# ProPrj_CGM_BH66F2452_HT32F67595_V1_0.net
KiCad netlist of a schematic drawn in EasyEDA Pro
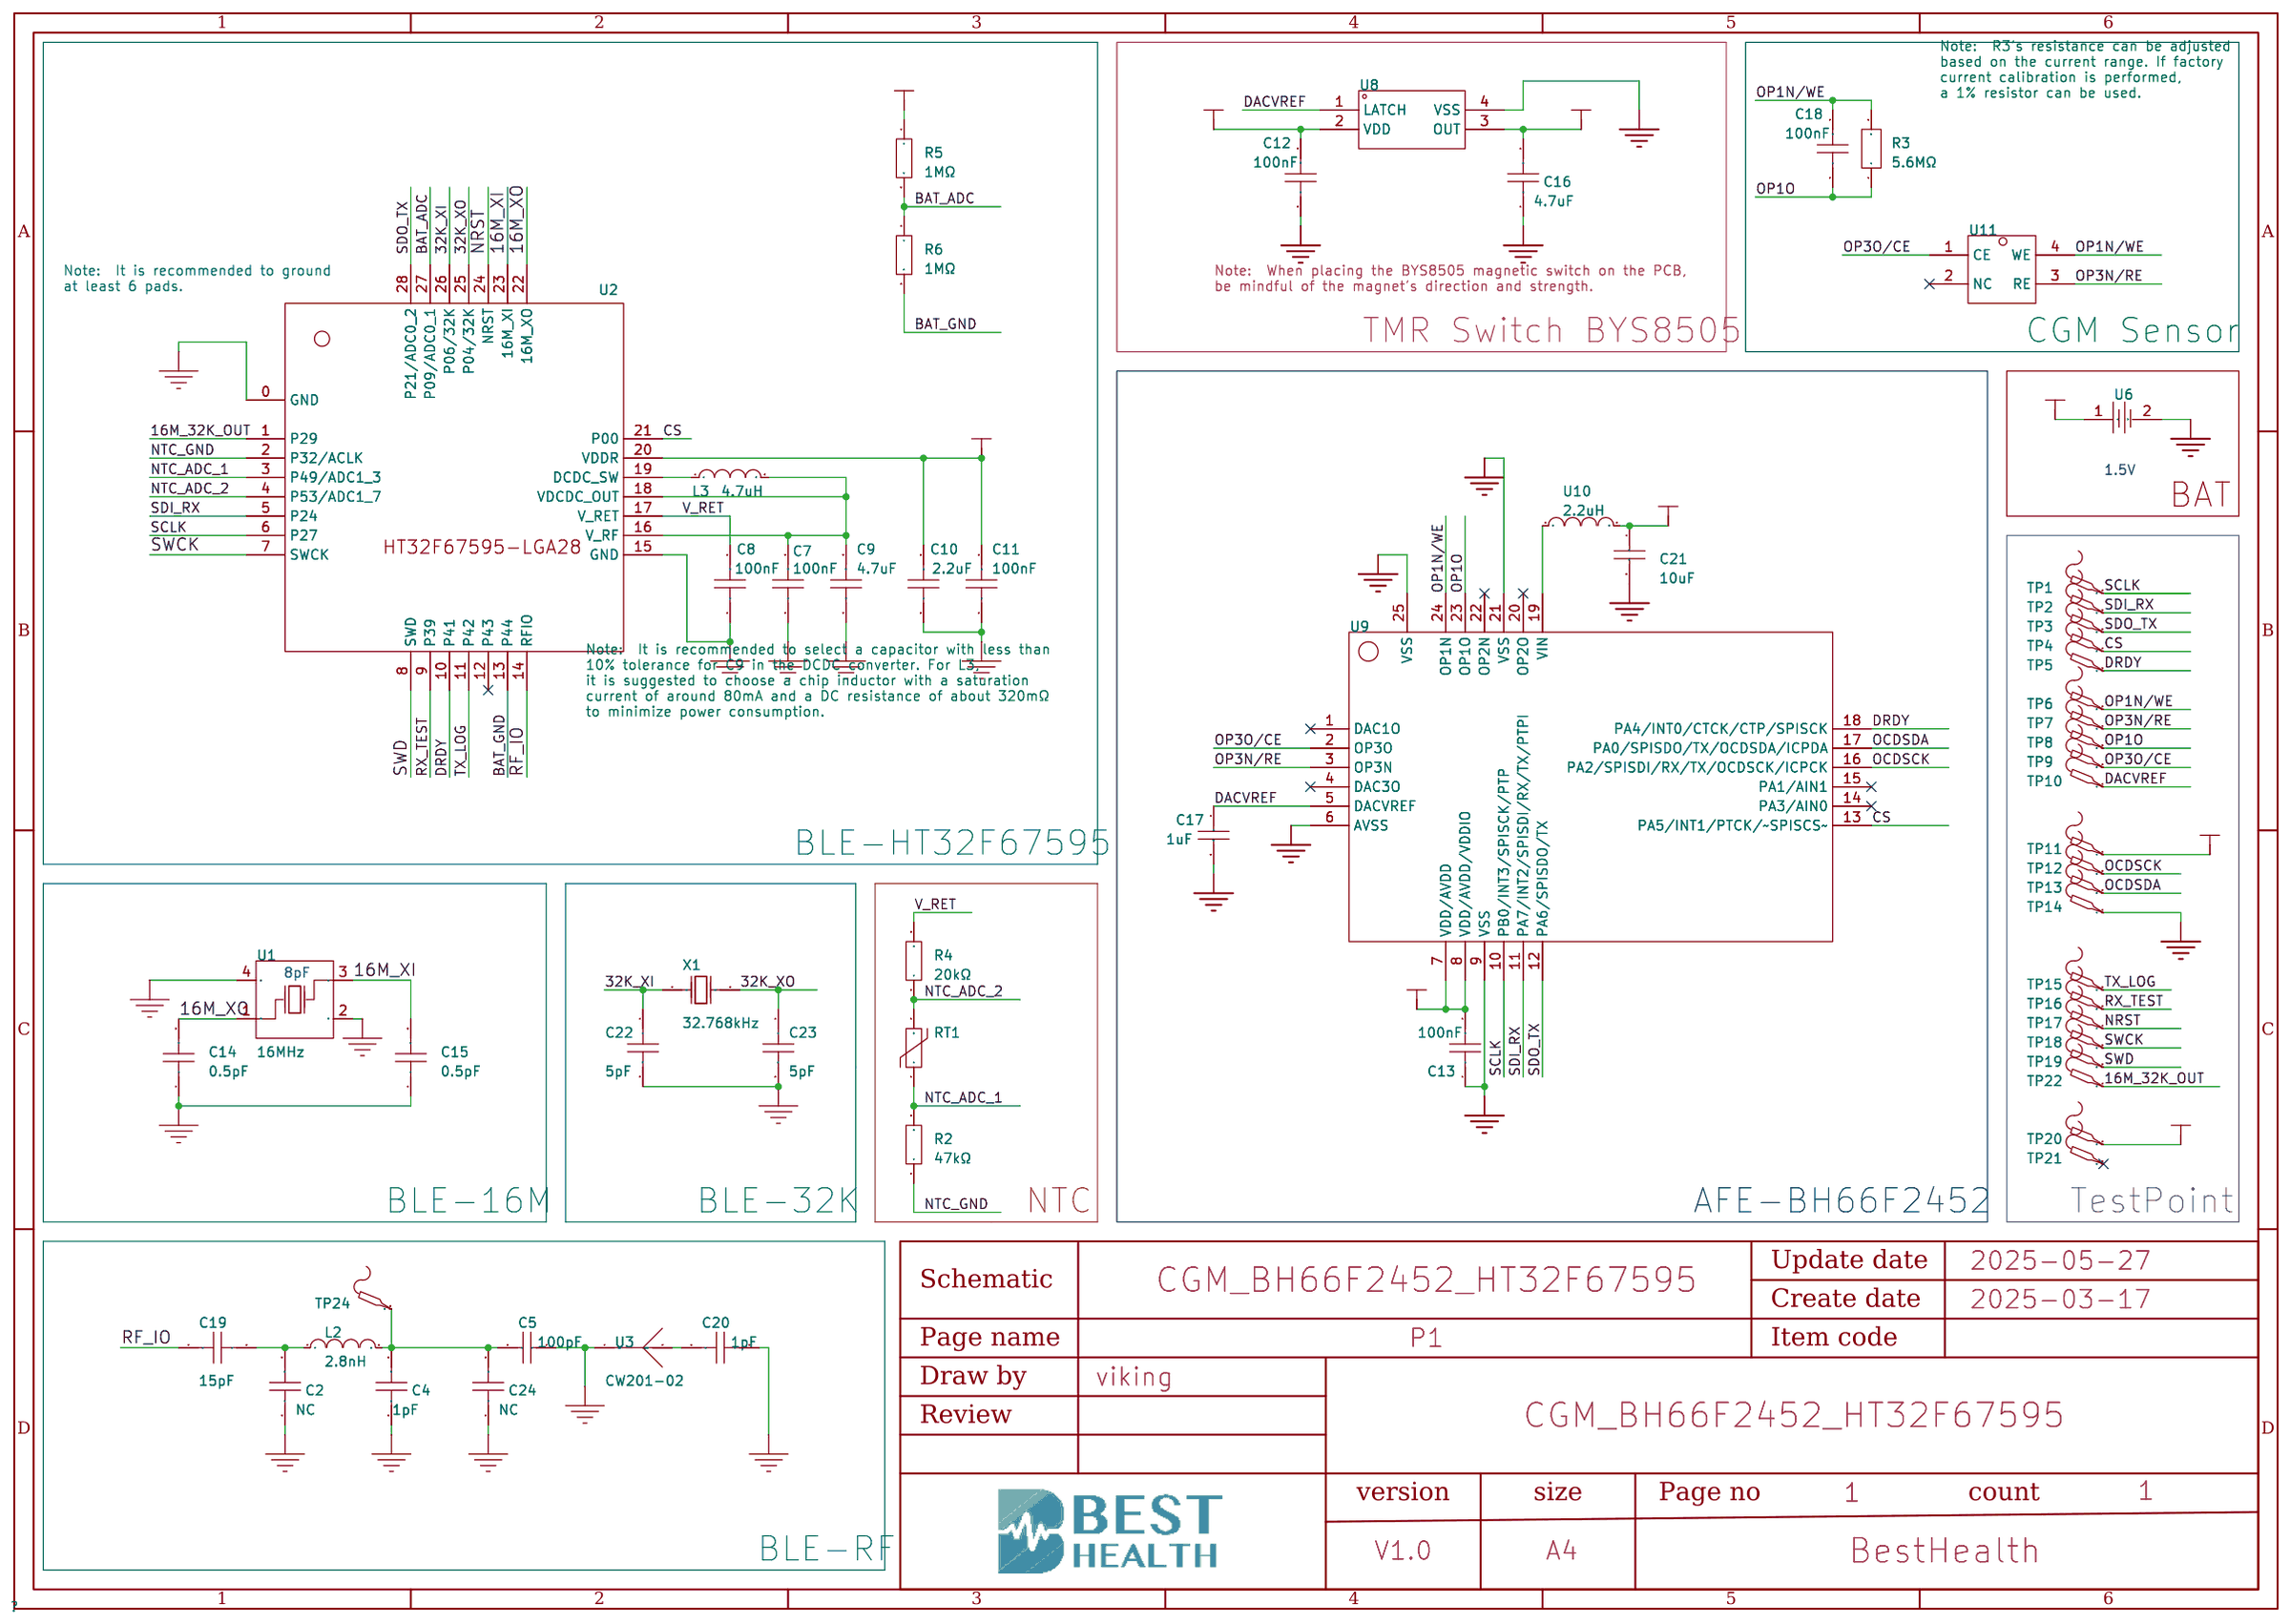
[diagram p0: schematic sheet]

(export (version "E")
  (design (tool "Eeschema 10.0.6"))
  (components
    (comp (ref "C2")
      (value "1.2pF")
      (footprint "easyedapro:C0201")
      (description "容值:1.2pF;额定电压:50V;材质(温度系数):C0G;")
      (fields
        (field (name "Manufacturer Part") "GJM0335C1H1R2WB01D")
        (field (name "Manufacturer") "muRata(村田)")
      )
      (libsource (lib "easyedapro") (part "GJM0335C1H1R2WB01D"))
    )
    (comp (ref "C4")
      (value "1pF")
      (footprint "easyedapro:C0201")
      (description "容值:1pF;精度:-;额定电压:50V;材质(温度系数):C0G;")
      (fields
        (field (name "Manufacturer Part") "GRM0335C1H1R0BA01D")
        (field (name "Manufacturer") "muRata(村田)")
      )
      (libsource (lib "easyedapro") (part "GRM0335C1H1R0BA01D"))
    )
    (comp (ref "C5")
      (value "100pF")
      (footprint "easyedapro:C0201")
      (description "容值:100pF;精度:±5%;额定电压:50V;材质(温度系数):C0G;")
      (fields
        (field (name "Manufacturer Part") "GRM0335C1H101JA01D")
        (field (name "Manufacturer") "muRata(村田)")
      )
      (libsource (lib "easyedapro") (part "GRM0335C1H101JA01D"))
    )
    (comp (ref "C7")
      (value "100nF")
      (footprint "easyedapro:C0201")
      (description "容值:100nF;精度:±10%;额定电压:16V;材质(温度系数):X5R;")
      (fields
        (field (name "Manufacturer Part") "CL03A104KO3NNNC")
        (field (name "Manufacturer") "SAMSUNG(三星)")
      )
      (libsource (lib "easyedapro") (part "CL03A104KO3NNNC"))
    )
    (comp (ref "C8")
      (value "100nF")
      (footprint "easyedapro:C0201")
      (description "容值:100nF;精度:±10%;额定电压:16V;材质(温度系数):X5R;")
      (fields
        (field (name "Manufacturer Part") "CL03A104KO3NNNC")
        (field (name "Manufacturer") "SAMSUNG(三星)")
      )
      (libsource (lib "easyedapro") (part "CL03A104KO3NNNC"))
    )
    (comp (ref "C9")
      (value "4.7uF")
      (footprint "easyedapro:C0402")
      (description "容值:4.7uF;精度:±10%;额定电压:10V;材质(温度系数):X5R;")
      (fields
        (field (name "Manufacturer Part") "CL05A475KP5NRNC")
        (field (name "Manufacturer") "SAMSUNG(三星)")
      )
      (libsource (lib "easyedapro") (part "CL05A475KP5NRNC"))
    )
    (comp (ref "C10")
      (value "2.2uF")
      (footprint "easyedapro:C0201")
      (description "容值:2.2uF;精度:±20%;额定电压:10V;材质(温度系数):X5R;")
      (fields
        (field (name "Manufacturer Part") "GRM033R61A225ME47D")
        (field (name "Manufacturer") "muRata(村田)")
      )
      (libsource (lib "easyedapro") (part "GRM033R61A225ME47D"))
    )
    (comp (ref "C11")
      (value "100nF")
      (footprint "easyedapro:C0201")
      (description "容值:100nF;精度:±10%;额定电压:16V;材质(温度系数):X5R;")
      (fields
        (field (name "Manufacturer Part") "CL03A104KO3NNNC")
        (field (name "Manufacturer") "SAMSUNG(三星)")
      )
      (libsource (lib "easyedapro") (part "CL03A104KO3NNNC"))
    )
    (comp (ref "C12")
      (value "100nF")
      (footprint "easyedapro:C0201")
      (description "容值:100nF;精度:±10%;额定电压:16V;材质(温度系数):X5R;")
      (fields
        (field (name "Manufacturer Part") "CL03A104KO3NNNC")
        (field (name "Manufacturer") "SAMSUNG(三星)")
      )
      (libsource (lib "easyedapro") (part "CL03A104KO3NNNC"))
    )
    (comp (ref "C13")
      (value "100nF")
      (footprint "easyedapro:C0201")
      (description "容值:100nF;精度:±10%;额定电压:16V;材质(温度系数):X5R;")
      (fields
        (field (name "Manufacturer Part") "CL03A104KO3NNNC")
        (field (name "Manufacturer") "SAMSUNG(三星)")
      )
      (libsource (lib "easyedapro") (part "CL03A104KO3NNNC"))
    )
    (comp (ref "C14")
      (value "0.5pF")
      (footprint "easyedapro:C0201")
      (description "容值:0.5pF;额定电压:50V;温度系数:C0G;")
      (fields
        (field (name "Manufacturer Part") "GRM0335C1HR50BA01D")
        (field (name "Manufacturer") "muRata(村田)")
      )
      (libsource (lib "easyedapro") (part "GRM0335C1HR50BA01D"))
    )
    (comp (ref "C15")
      (value "0.5pF")
      (footprint "easyedapro:C0201")
      (description "容值:0.5pF;额定电压:50V;温度系数:C0G;")
      (fields
        (field (name "Manufacturer Part") "GRM0335C1HR50BA01D")
        (field (name "Manufacturer") "muRata(村田)")
      )
      (libsource (lib "easyedapro") (part "GRM0335C1HR50BA01D"))
    )
    (comp (ref "C16")
      (value "4.7uF")
      (footprint "easyedapro:C0201")
      (description "容值:4.7uF;精度:±20%;额定电压:6.3V;材质(温度系数):X5R;")
      (fields
        (field (name "Manufacturer Part") "GRM035R60J475ME15D")
        (field (name "Manufacturer") "muRata(村田)")
      )
      (libsource (lib "easyedapro") (part "GRM035R60J475ME15D"))
    )
    (comp (ref "C17")
      (value "1uF")
      (footprint "easyedapro:C0201")
      (description "容值:1uF;精度:±20%;额定电压:6.3V;材质(温度系数):X5R;")
      (fields
        (field (name "Manufacturer Part") "CL03A105MQ3CSNH")
        (field (name "Manufacturer") "SAMSUNG(三星)")
      )
      (libsource (lib "easyedapro") (part "CL03A105MQ3CSNH"))
    )
    (comp (ref "C18")
      (value "100nF")
      (footprint "easyedapro:C0201")
      (description "容值:100nF;精度:±10%;额定电压:16V;材质(温度系数):X5R;")
      (fields
        (field (name "Manufacturer Part") "CL03A104KO3NNNC")
        (field (name "Manufacturer") "SAMSUNG(三星)")
      )
      (libsource (lib "easyedapro") (part "CL03A104KO3NNNC"))
    )
    (comp (ref "C19")
      (value "15pF")
      (footprint "easyedapro:C0201")
      (description "容值:15pF;精度:±5%;额定电压:50V;温度系数:C0G;")
      (fields
        (field (name "Manufacturer Part") "GRM0335C1H150JA01D")
        (field (name "Manufacturer") "muRata(村田)")
      )
      (libsource (lib "easyedapro") (part "GRM0335C1H150JA01D"))
    )
    (comp (ref "C20")
      (value "1pF")
      (footprint "easyedapro:C0201")
      (description "容值:1pF;精度:-;额定电压:50V;材质(温度系数):C0G;")
      (fields
        (field (name "Manufacturer Part") "GRM0335C1H1R0BA01D")
        (field (name "Manufacturer") "muRata(村田)")
      )
      (libsource (lib "easyedapro") (part "GRM0335C1H1R0BA01D"))
    )
    (comp (ref "C21")
      (value "10uF")
      (footprint "easyedapro:C0402")
      (description "容值:10uF;精度:±20%;额定电压:6.3V;材质(温度系数):X5R;")
      (fields
        (field (name "Manufacturer Part") "CL05A106MQ5NUNC")
        (field (name "Manufacturer") "SAMSUNG(三星)")
      )
      (libsource (lib "easyedapro") (part "CL05A106MQ5NUNC"))
    )
    (comp (ref "C22")
      (value "5pF")
      (footprint "easyedapro:C0201")
      (description "容值:5pF;额定电压:25V;材质(温度系数):C0G;")
      (fields
        (field (name "Manufacturer Part") "GJM0335C1E5R0BB01D")
        (field (name "Manufacturer") "muRata(村田)")
      )
      (libsource (lib "easyedapro") (part "GJM0335C1E5R0BB01D"))
    )
    (comp (ref "C23")
      (value "5pF")
      (footprint "easyedapro:C0201")
      (description "容值:5pF;额定电压:25V;材质(温度系数):C0G;")
      (fields
        (field (name "Manufacturer Part") "GJM0335C1E5R0BB01D")
        (field (name "Manufacturer") "muRata(村田)")
      )
      (libsource (lib "easyedapro") (part "GJM0335C1E5R0BB01D"))
    )
    (comp (ref "C24")
      (value "1.2pF")
      (footprint "easyedapro:C0201")
      (description "容值:1.2pF;额定电压:50V;材质(温度系数):C0G;")
      (fields
        (field (name "Manufacturer Part") "GJM0335C1H1R2WB01D")
        (field (name "Manufacturer") "muRata(村田)")
      )
      (libsource (lib "easyedapro") (part "GJM0335C1H1R2WB01D"))
    )
    (comp (ref "L2")
      (value "2.8nH")
      (footprint "easyedapro:L0201-RD")
      (description "电感值:2.8nH;精度:-;额定电流:450mA;饱和电流(Isat):-;直流电阻(DCR):250mΩ;")
      (fields (field (name "Manufacturer Part") "LQP03TG2N8B02D") (field (name "Manufacturer") "muRata(村田)"))
      (libsource (lib "easyedapro") (part "LQP03TG2N8B02D"))
    )
    (comp (ref "L3")
      (value "4.7uH")
      (footprint "easyedapro:L0603")
      (description "电感值:4.7uH;精度:±20%;额定电流:-;饱和电流(Isat):80mA;直流电阻(DCR):320mΩ;")
      (fields (field (name "Manufacturer Part") "MLZ1608N4R7LT000") (field (name "Manufacturer") "TDK"))
      (libsource (lib "easyedapro") (part "MLZ1608N4R7LT000"))
    )
    (comp (ref "R2")
      (value "47kΩ")
      (footprint "easyedapro:R0201")
      (description "电阻类型:厚膜电阻;阻值:47kΩ;精度:±1%;功率:50mW;温度系数:±200ppm/°C;最大工作电压:25V;工作温度范围:-55°C~+155°C;")
      (fields (field (name "Manufacturer Part") "RC0201FR-0747KL") (field (name "Manufacturer") "YAGEO(国巨)"))
      (libsource (lib "easyedapro") (part "RC0201FR-0747KL"))
    )
    (comp (ref "R3")
      (value "5.6MΩ")
      (footprint "easyedapro:R0402")
      (description "电阻类型:厚膜电阻;阻值:5.6MΩ;精度:±1%;功率:62.5mW;最大工作电压:50V;温度系数:±100ppm/°C;")
      (fields (field (name "Manufacturer Part") "RC0402FR-075M6L") (field (name "Manufacturer") "YAGEO(国巨)"))
      (libsource (lib "easyedapro") (part "RC0402FR-075M6L"))
    )
    (comp (ref "R4")
      (value "20kΩ")
      (footprint "easyedapro:R0201")
      (description "电阻类型:厚膜电阻;阻值:20kΩ;精度:±1%;功率:50mW;最大工作电压:25V;温度系数:±200ppm/°C;")
      (fields (field (name "Manufacturer Part") "RC0201FR-0720KL") (field (name "Manufacturer") "YAGEO(国巨)"))
      (libsource (lib "easyedapro") (part "RC0201FR-0720KL_C295787"))
    )
    (comp (ref "R5")
      (value "1MΩ")
      (footprint "easyedapro:R0201")
      (description "电阻类型:厚膜电阻;阻值:1MΩ;精度:±1%;功率:50mW;最大工作电压:25V;温度系数:±200ppm/°C;")
      (fields (field (name "Manufacturer Part") "RC0201FR-071ML") (field (name "Manufacturer") "YAGEO(国巨)"))
      (libsource (lib "easyedapro") (part "RC0201FR-071ML"))
    )
    (comp (ref "R6")
      (value "1MΩ")
      (footprint "easyedapro:R0201")
      (description "电阻类型:厚膜电阻;阻值:1MΩ;精度:±1%;功率:50mW;最大工作电压:25V;温度系数:±200ppm/°C;")
      (fields (field (name "Manufacturer Part") "RC0201FR-071ML") (field (name "Manufacturer") "YAGEO(国巨)"))
      (libsource (lib "easyedapro") (part "RC0201FR-071ML"))
    )
    (comp (ref "RT1")
      (value "NTCG064BF473FTBX")
      (footprint "easyedapro:R0201")
      (description "阻值(25°C):47kΩ;电阻精度:±1%;B值精度:±1%;B值(25°C/50°C):4050K;功率:100mW;最大稳态电流(25°C):140uA;")
      (fields (field (name "Manufacturer") "TDK"))
      (libsource (lib "easyedapro") (part "NTCG064BF473FTBX"))
    )
    (comp (ref "TP1")
      (value "TP1")
      (footprint "easyedapro:Test-Point-0.5mm")
      (description "Test Point 测试点")
      (libsource (lib "easyedapro") (part "Test-Point"))
    )
    (comp (ref "TP2")
      (value "TP1")
      (footprint "easyedapro:Test-Point-0.5mm")
      (description "Test Point 测试点")
      (libsource (lib "easyedapro") (part "Test-Point"))
    )
    (comp (ref "TP3")
      (value "TP1")
      (footprint "easyedapro:Test-Point-0.5mm")
      (description "Test Point 测试点")
      (libsource (lib "easyedapro") (part "Test-Point"))
    )
    (comp (ref "TP4")
      (value "TP1")
      (footprint "easyedapro:Test-Point-0.5mm")
      (description "Test Point 测试点")
      (libsource (lib "easyedapro") (part "Test-Point"))
    )
    (comp (ref "TP5")
      (value "TP1")
      (footprint "easyedapro:Test-Point-0.5mm")
      (description "Test Point 测试点")
      (libsource (lib "easyedapro") (part "Test-Point"))
    )
    (comp (ref "TP6")
      (value "TP1")
      (footprint "easyedapro:Test-Point-0.5mm")
      (description "Test Point 测试点")
      (libsource (lib "easyedapro") (part "Test-Point"))
    )
    (comp (ref "TP7")
      (value "TP1")
      (footprint "easyedapro:Test-Point-0.5mm")
      (description "Test Point 测试点")
      (libsource (lib "easyedapro") (part "Test-Point"))
    )
    (comp (ref "TP8")
      (value "TP1")
      (footprint "easyedapro:Test-Point-0.5mm")
      (description "Test Point 测试点")
      (libsource (lib "easyedapro") (part "Test-Point"))
    )
    (comp (ref "TP9")
      (value "TP1")
      (footprint "easyedapro:Test-Point-0.5mm")
      (description "Test Point 测试点")
      (libsource (lib "easyedapro") (part "Test-Point"))
    )
    (comp (ref "TP10")
      (value "TP1")
      (footprint "easyedapro:Test-Point-0.5mm")
      (description "Test Point 测试点")
      (libsource (lib "easyedapro") (part "Test-Point"))
    )
    (comp (ref "TP11")
      (value "TP1")
      (footprint "easyedapro:Test-Point-0.5mm")
      (description "Test Point 测试点")
      (libsource (lib "easyedapro") (part "Test-Point"))
    )
    (comp (ref "TP12")
      (value "TP1")
      (footprint "easyedapro:Test-Point-0.5mm")
      (description "Test Point 测试点")
      (libsource (lib "easyedapro") (part "Test-Point"))
    )
    (comp (ref "TP13")
      (value "TP1")
      (footprint "easyedapro:Test-Point-0.5mm")
      (description "Test Point 测试点")
      (libsource (lib "easyedapro") (part "Test-Point"))
    )
    (comp (ref "TP14")
      (value "TP1")
      (footprint "easyedapro:Test-Point-0.5mm")
      (description "Test Point 测试点")
      (libsource (lib "easyedapro") (part "Test-Point"))
    )
    (comp (ref "TP15")
      (value "~")
      (footprint "easyedapro:Test-Point-0.5mm")
      (description "Test Point 测试点")
      (libsource (lib "easyedapro") (part "Test-Point"))
    )
    (comp (ref "TP16")
      (value "~")
      (footprint "easyedapro:Test-Point-0.5mm")
      (description "Test Point 测试点")
      (libsource (lib "easyedapro") (part "Test-Point"))
    )
    (comp (ref "TP17")
      (value "~")
      (footprint "easyedapro:Test-Point-0.5mm")
      (description "Test Point 测试点")
      (libsource (lib "easyedapro") (part "Test-Point"))
    )
    (comp (ref "TP18")
      (value "~")
      (footprint "easyedapro:Test-Point-0.5mm")
      (description "Test Point 测试点")
      (libsource (lib "easyedapro") (part "Test-Point"))
    )
    (comp (ref "TP19")
      (value "~")
      (footprint "easyedapro:Test-Point-0.5mm")
      (description "Test Point 测试点")
      (libsource (lib "easyedapro") (part "Test-Point"))
    )
    (comp (ref "TP20")
      (value "~")
      (footprint "easyedapro:Test-Point-0.5mm")
      (description "Test Point 测试点")
      (libsource (lib "easyedapro") (part "Test-Point"))
    )
    (comp (ref "TP21")
      (value "~")
      (footprint "easyedapro:Test-Point-0.5mm")
      (description "Test Point 测试点")
      (libsource (lib "easyedapro") (part "Test-Point"))
    )
    (comp (ref "TP22")
      (value "~")
      (footprint "easyedapro:Test-Point-0.5mm")
      (description "Test Point 测试点")
      (libsource (lib "easyedapro") (part "Test-Point"))
    )
    (comp (ref "TP24")
      (value "~")
      (footprint "easyedapro:Test-Point-0.5mm")
      (description "Test Point 测试点")
      (libsource (lib "easyedapro") (part "Test-Point"))
    )
    (comp (ref "U1")
      (value "16MHz")
      (footprint "easyedapro:CRYSTAL-SMD_4P-L2.0-W1.6-BL-A")
      (description "频率:16MHz;负载电容:8pF;频率公差:±10ppm;")
      (fields
        (field (name "Manufacturer Part") "XL7EL89CKI-111YLC-16M")
        (field (name "Manufacturer") "YXC(扬兴晶振)")
      )
      (libsource (lib "easyedapro") (part "XL7EL89CKI-111YLC-16M"))
    )
    (comp (ref "U2")
      (value "HT32F67595_LGA28")
      (footprint "easyedapro:LGA28_L3.0_W3.0mm")
      (libsource (lib "easyedapro") (part "HT32F67595_LGA28"))
    )
    (comp (ref "U3")
      (value "CW201-02")
      (footprint "easyedapro:ANT-SMD_L2.0-W1.2_CW201")
      (fields (field (name "Manufacturer") "LXC(连兴创)"))
      (libsource (lib "easyedapro") (part "CW201-02"))
    )
    (comp (ref "U6")
      (value "~")
      (footprint "easyedapro:SR716")
      (description "氧化銀紐扣電池1.5V")
      (libsource (lib "easyedapro") (part "SR716"))
    )
    (comp (ref "U8")
      (value "~")
      (footprint "easyedapro:LGA-4_L1.5-W1.5-P0.65-BL")
      (libsource (lib "easyedapro") (part "BYS8505"))
    )
    (comp (ref "U9")
      (value "~")
      (footprint "easyedapro:WQFN-24_L3.0-W3.0-P0.40-TL-EP1.9")
      (description "该单片机是一款 A/D 型具有 8 位高性能精简指令集的 Flash 单片机，内置连续\n血糖监测 AFE 模块，专门为连续血糖监测产品而设计。")
      (fields (field (name "Manufacturer") "HOLTEK"))
      (libsource (lib "easyedapro") (part "BH66F2452"))
    )
    (comp (ref "U10")
      (value "2.2uH")
      (footprint "easyedapro:IND-SMD_L2.0-W1.6")
      (description "电感值:2.2uH;精度:±20%;额定电流:1.31A;饱和电流(Isat):1.31A;")
      (fields (field (name "Manufacturer Part") "VLS201610CX-2R2M-1") (field (name "Manufacturer") "TDK"))
      (libsource (lib "easyedapro") (part "VLS201610CX-2R2M-1"))
    )
    (comp (ref "U11")
      (value "~")
      (footprint "easyedapro:CGM_Sener_V2_TBJ")
      (libsource (lib "easyedapro") (part "CGM_Sensor_V2_TBJ"))
    )
    (comp (ref "X1")
      (value "32.768kHz")
      (footprint "easyedapro:CRYSTAL-SMD_L1.7-W1.1")
      (description "频率:32.768kHz;外接负载电容:12.5pF;")
      (fields (field (name "Manufacturer Part") "X1A0001210005") (field (name "Manufacturer") "EPSON(爱普生)"))
      (libsource (lib "easyedapro") (part "X1A000121000500"))
    )
  )
  (nets
    (net (code "1") (name "/16M_32K_OUT") (class "Default")
      (node (ref "TP22") (pin "1") (pinfunction "1_1") (pintype "input"))
      (node (ref "U2") (pin "1") (pinfunction "P29_1") (pintype "input"))
    )
    (net (code "2") (name "/16M_XI") (class "Default")
      (node (ref "C15") (pin "2") (pinfunction "2_2") (pintype "unspecified"))
      (node (ref "U1") (pin "3") (pinfunction "OSC2_3") (pintype "unspecified"))
      (node (ref "U2") (pin "23") (pinfunction "16M_XI_23") (pintype "input"))
    )
    (net (code "3") (name "/16M_XO") (class "Default")
      (node (ref "C14") (pin "2") (pinfunction "2_2") (pintype "unspecified"))
      (node (ref "U1") (pin "1") (pinfunction "OSC1_1") (pintype "unspecified"))
      (node (ref "U2") (pin "22") (pinfunction "16M_XO_22") (pintype "input"))
    )
    (net (code "4") (name "/32K_XI") (class "Default")
      (node (ref "C22") (pin "1") (pinfunction "1_1") (pintype "unspecified"))
      (node (ref "U2") (pin "26") (pinfunction "P06/32K_26") (pintype "input"))
      (node (ref "X1") (pin "1") (pinfunction "OSC1_1") (pintype "input"))
    )
    (net (code "5") (name "/32K_XO") (class "Default")
      (node (ref "C23") (pin "1") (pinfunction "1_1") (pintype "unspecified"))
      (node (ref "U2") (pin "25") (pinfunction "P04/32K_25") (pintype "input"))
      (node (ref "X1") (pin "2") (pinfunction "OSC2_2") (pintype "input"))
    )
    (net (code "6") (name "/BAT_ADC") (class "Default")
      (node (ref "R5") (pin "2") (pinfunction "2_2") (pintype "unspecified"))
      (node (ref "R6") (pin "1") (pinfunction "1_1") (pintype "unspecified"))
      (node (ref "U2") (pin "27") (pinfunction "P09/ADC0_1_27") (pintype "input"))
    )
    (net (code "7") (name "/BAT_GND") (class "Default")
      (node (ref "R6") (pin "2") (pinfunction "2_2") (pintype "unspecified"))
      (node (ref "U2") (pin "13") (pinfunction "P44_13") (pintype "input"))
    )
    (net (code "8") (name "/CS") (class "Default")
      (node (ref "TP4") (pin "1") (pinfunction "1_1") (pintype "input"))
      (node (ref "U2") (pin "21") (pinfunction "P00_21") (pintype "input"))
      (node (ref "U9") (pin "13") (pinfunction "PA5/INT1/PTCK/~SPISCS~_13") (pintype "input"))
    )
    (net (code "9") (name "/DACVREF") (class "Default")
      (node (ref "C17") (pin "1") (pinfunction "1_1") (pintype "input"))
      (node (ref "TP10") (pin "1") (pinfunction "1_1") (pintype "input"))
      (node (ref "U8") (pin "1") (pinfunction "LATCH_1") (pintype "input"))
      (node (ref "U9") (pin "5") (pinfunction "DACVREF_5") (pintype "input"))
    )
    (net (code "10") (name "/DRDY") (class "Default")
      (node (ref "TP5") (pin "1") (pinfunction "1_1") (pintype "input"))
      (node (ref "U2") (pin "10") (pinfunction "P41_10") (pintype "input"))
      (node (ref "U9") (pin "18") (pinfunction "PA4/INT0/CTCK/CTP/SPISCK_18") (pintype "input"))
    )
    (net (code "11") (name "/NRST") (class "Default")
      (node (ref "TP17") (pin "1") (pinfunction "1_1") (pintype "input"))
      (node (ref "U2") (pin "24") (pinfunction "NRST_24") (pintype "input"))
    )
    (net (code "12") (name "/NTC_ADC_1") (class "Default")
      (node (ref "R2") (pin "2") (pinfunction "2_2") (pintype "input"))
      (node (ref "RT1") (pin "1") (pinfunction "1_1") (pintype "input"))
      (node (ref "U2") (pin "3") (pinfunction "P49/ADC1_3_3") (pintype "input"))
    )
    (net (code "13") (name "/NTC_ADC_2") (class "Default")
      (node (ref "R4") (pin "1") (pinfunction "1_1") (pintype "unspecified"))
      (node (ref "RT1") (pin "2") (pinfunction "2_2") (pintype "input"))
      (node (ref "U2") (pin "4") (pinfunction "P53/ADC1_7_4") (pintype "input"))
    )
    (net (code "14") (name "/NTC_GND") (class "Default")
      (node (ref "R2") (pin "1") (pinfunction "1_1") (pintype "input"))
      (node (ref "U2") (pin "2") (pinfunction "P32/ACLK_2") (pintype "input"))
    )
    (net (code "15") (name "/OCDSCK") (class "Default")
      (node (ref "TP12") (pin "1") (pinfunction "1_1") (pintype "input"))
      (node (ref "U9") (pin "16") (pinfunction "PA2/SPISDI/RX/TX/OCDSCK/ICPCK_16") (pintype "input"))
    )
    (net (code "16") (name "/OCDSDA") (class "Default")
      (node (ref "TP13") (pin "1") (pinfunction "1_1") (pintype "input"))
      (node (ref "U9") (pin "17") (pinfunction "PA0/SPISDO/TX/OCDSDA/ICPDA_17") (pintype "input"))
    )
    (net (code "17") (name "/OP1N{slash}WE") (class "Default")
      (node (ref "C18") (pin "2") (pinfunction "2_2") (pintype "input"))
      (node (ref "R3") (pin "2") (pinfunction "2_2") (pintype "unspecified"))
      (node (ref "TP6") (pin "1") (pinfunction "1_1") (pintype "input"))
      (node (ref "U11") (pin "4") (pinfunction "WE_4") (pintype "input"))
      (node (ref "U9") (pin "24") (pinfunction "OP1N_24") (pintype "input"))
    )
    (net (code "18") (name "/OP1O") (class "Default")
      (node (ref "C18") (pin "1") (pinfunction "1_1") (pintype "input"))
      (node (ref "R3") (pin "1") (pinfunction "1_1") (pintype "unspecified"))
      (node (ref "TP8") (pin "1") (pinfunction "1_1") (pintype "input"))
      (node (ref "U9") (pin "23") (pinfunction "OP1O_23") (pintype "input"))
    )
    (net (code "19") (name "/OP3N{slash}RE") (class "Default")
      (node (ref "TP7") (pin "1") (pinfunction "1_1") (pintype "input"))
      (node (ref "U11") (pin "3") (pinfunction "RE_3") (pintype "input"))
      (node (ref "U9") (pin "3") (pinfunction "OP3N_3") (pintype "input"))
    )
    (net (code "20") (name "/OP3O{slash}CE") (class "Default")
      (node (ref "TP9") (pin "1") (pinfunction "1_1") (pintype "input"))
      (node (ref "U11") (pin "1") (pinfunction "CE_1") (pintype "input"))
      (node (ref "U9") (pin "2") (pinfunction "OP3O_2") (pintype "input"))
    )
    (net (code "21") (name "/RF_IO") (class "Default")
      (node (ref "C19") (pin "1") (pinfunction "1_1") (pintype "unspecified"))
      (node (ref "U2") (pin "14") (pinfunction "RFIO_14") (pintype "input"))
    )
    (net (code "22") (name "/RX_TEST") (class "Default")
      (node (ref "TP16") (pin "1") (pinfunction "1_1") (pintype "input"))
      (node (ref "U2") (pin "9") (pinfunction "P39_9") (pintype "input"))
    )
    (net (code "23") (name "/SCLK") (class "Default")
      (node (ref "TP1") (pin "1") (pinfunction "1_1") (pintype "input"))
      (node (ref "U2") (pin "6") (pinfunction "P27_6") (pintype "input"))
      (node (ref "U9") (pin "10") (pinfunction "PB0/INT3/SPISCK/PTP_10") (pintype "input"))
    )
    (net (code "24") (name "/SDI_RX") (class "Default")
      (node (ref "TP2") (pin "1") (pinfunction "1_1") (pintype "input"))
      (node (ref "U2") (pin "5") (pinfunction "P24_5") (pintype "input"))
      (node (ref "U9") (pin "11") (pinfunction "PA7/INT2/SPISDI/RX/TX/PTPI_11") (pintype "input"))
    )
    (net (code "25") (name "/SDO_TX") (class "Default")
      (node (ref "TP3") (pin "1") (pinfunction "1_1") (pintype "input"))
      (node (ref "U2") (pin "28") (pinfunction "P21/ADC0_2_28") (pintype "input"))
      (node (ref "U9") (pin "12") (pinfunction "PA6/SPISDO/TX_12") (pintype "input"))
    )
    (net (code "26") (name "/SWCK") (class "Default")
      (node (ref "TP18") (pin "1") (pinfunction "1_1") (pintype "input"))
      (node (ref "U2") (pin "7") (pinfunction "SWCK_7") (pintype "input"))
    )
    (net (code "27") (name "/SWD") (class "Default")
      (node (ref "TP19") (pin "1") (pinfunction "1_1") (pintype "input"))
      (node (ref "U2") (pin "8") (pinfunction "SWD_8") (pintype "input"))
    )
    (net (code "28") (name "/TX_LOG") (class "Default")
      (node (ref "TP15") (pin "1") (pinfunction "1_1") (pintype "input"))
      (node (ref "U2") (pin "11") (pinfunction "P42_11") (pintype "input"))
    )
    (net (code "29") (name "/V_RET") (class "Default")
      (node (ref "C8") (pin "2") (pinfunction "2_2") (pintype "input"))
      (node (ref "R4") (pin "2") (pinfunction "2_2") (pintype "unspecified"))
      (node (ref "U2") (pin "17") (pinfunction "V_RET_17") (pintype "input"))
    )
    (net (code "30") (name "GND") (class "Default")
      (node (ref "C10") (pin "1") (pinfunction "1_1") (pintype "unspecified"))
      (node (ref "C11") (pin "1") (pinfunction "1_1") (pintype "input"))
      (node (ref "C12") (pin "1") (pinfunction "1_1") (pintype "input"))
      (node (ref "C13") (pin "1") (pinfunction "1_1") (pintype "input"))
      (node (ref "C14") (pin "1") (pinfunction "1_1") (pintype "unspecified"))
      (node (ref "C15") (pin "1") (pinfunction "1_1") (pintype "unspecified"))
      (node (ref "C16") (pin "1") (pinfunction "1_1") (pintype "unspecified"))
      (node (ref "C17") (pin "2") (pinfunction "2_2") (pintype "input"))
      (node (ref "C2") (pin "1") (pinfunction "1_1") (pintype "unspecified"))
      (node (ref "C20") (pin "1") (pinfunction "1_1") (pintype "unspecified"))
      (node (ref "C21") (pin "2") (pinfunction "2_2") (pintype "input"))
      (node (ref "C22") (pin "2") (pinfunction "2_2") (pintype "unspecified"))
      (node (ref "C23") (pin "2") (pinfunction "2_2") (pintype "unspecified"))
      (node (ref "C24") (pin "1") (pinfunction "1_1") (pintype "unspecified"))
      (node (ref "C4") (pin "1") (pinfunction "1_1") (pintype "unspecified"))
      (node (ref "C5") (pin "2") (pinfunction "2_2") (pintype "input"))
      (node (ref "C7") (pin "1") (pinfunction "1_1") (pintype "input"))
      (node (ref "C8") (pin "1") (pinfunction "1_1") (pintype "input"))
      (node (ref "C9") (pin "1") (pinfunction "1_1") (pintype "unspecified"))
      (node (ref "TP14") (pin "1") (pinfunction "1_1") (pintype "input"))
      (node (ref "U1") (pin "2") (pinfunction "GND_2") (pintype "unspecified"))
      (node (ref "U1") (pin "4") (pinfunction "GND_4") (pintype "unspecified"))
      (node (ref "U2") (pin "0") (pinfunction "GND_0") (pintype "input"))
      (node (ref "U2") (pin "15") (pinfunction "GND_15") (pintype "input"))
      (node (ref "U3") (pin "1") (pinfunction "Signal_Input_1") (pintype "unspecified"))
      (node (ref "U6") (pin "2") (pinfunction "2_2") (pintype "input"))
      (node (ref "U8") (pin "4") (pinfunction "VSS_4") (pintype "input"))
      (node (ref "U9") (pin "21") (pinfunction "VSS_21") (pintype "input"))
      (node (ref "U9") (pin "25") (pinfunction "VSS_25") (pintype "input"))
      (node (ref "U9") (pin "6") (pinfunction "AVSS_6") (pintype "input"))
      (node (ref "U9") (pin "9") (pinfunction "VSS_9") (pintype "input"))
    )
    (net (code "31") (name "Net-(C19-Pad2)") (class "Default")
      (node (ref "C19") (pin "2") (pinfunction "2_2") (pintype "unspecified"))
      (node (ref "C2") (pin "2") (pinfunction "2_2") (pintype "unspecified"))
      (node (ref "L2") (pin "1") (pinfunction "1_1") (pintype "unspecified"))
    )
    (net (code "32") (name "Net-(C24-Pad2)") (class "Default")
      (node (ref "C24") (pin "2") (pinfunction "2_2") (pintype "unspecified"))
      (node (ref "C4") (pin "2") (pinfunction "2_2") (pintype "unspecified"))
      (node (ref "C5") (pin "1") (pinfunction "1_1") (pintype "input"))
      (node (ref "L2") (pin "2") (pinfunction "2_2") (pintype "unspecified"))
      (node (ref "TP24") (pin "1") (pinfunction "1_1") (pintype "input"))
    )
    (net (code "33") (name "Net-(U2-DCDC_SW)") (class "Default")
      (node (ref "L3") (pin "1") (pinfunction "1_1") (pintype "unspecified"))
      (node (ref "U2") (pin "19") (pinfunction "DCDC_SW_19") (pintype "input"))
    )
    (net (code "34") (name "Net-(U2-VDCDC_OUT)") (class "Default")
      (node (ref "C7") (pin "2") (pinfunction "2_2") (pintype "input"))
      (node (ref "C9") (pin "2") (pinfunction "2_2") (pintype "unspecified"))
      (node (ref "L3") (pin "2") (pinfunction "2_2") (pintype "unspecified"))
      (node (ref "U2") (pin "16") (pinfunction "V_RF_16") (pintype "input"))
      (node (ref "U2") (pin "18") (pinfunction "VDCDC_OUT_18") (pintype "input"))
    )
    (net (code "35") (name "Net-(U3-Tuning{slash}Signal_Output)") (class "Default")
      (node (ref "C20") (pin "2") (pinfunction "2_2") (pintype "unspecified"))
      (node (ref "U3") (pin "2") (pinfunction "Tuning/Signal_Output_2") (pintype "unspecified"))
    )
    (net (code "36") (name "Net-(U9-VIN)") (class "Default")
      (node (ref "U10") (pin "1") (pinfunction "1_1") (pintype "unspecified"))
      (node (ref "U9") (pin "19") (pinfunction "VIN_19") (pintype "input"))
    )
    (net (code "37") (name "VBAT") (class "Default")
      (node (ref "C12") (pin "2") (pinfunction "2_2") (pintype "input"))
      (node (ref "R5") (pin "1") (pinfunction "1_1") (pintype "unspecified"))
      (node (ref "TP20") (pin "1") (pinfunction "1_1") (pintype "input"))
      (node (ref "U6") (pin "1") (pinfunction "1_1") (pintype "input"))
      (node (ref "U8") (pin "2") (pinfunction "VDD_2") (pintype "input"))
    )
    (net (code "38") (name "VBATO") (class "Default")
      (node (ref "C16") (pin "2") (pinfunction "2_2") (pintype "unspecified"))
      (node (ref "C21") (pin "1") (pinfunction "1_1") (pintype "input"))
      (node (ref "U10") (pin "2") (pinfunction "2_2") (pintype "unspecified"))
      (node (ref "U8") (pin "3") (pinfunction "OUT_3") (pintype "input"))
    )
    (net (code "39") (name "VDD") (class "Default")
      (node (ref "C10") (pin "2") (pinfunction "2_2") (pintype "unspecified"))
      (node (ref "C11") (pin "2") (pinfunction "2_2") (pintype "input"))
      (node (ref "C13") (pin "2") (pinfunction "2_2") (pintype "input"))
      (node (ref "TP11") (pin "1") (pinfunction "1_1") (pintype "input"))
      (node (ref "U2") (pin "20") (pinfunction "VDDR_20") (pintype "input"))
      (node (ref "U9") (pin "7") (pinfunction "VDD/AVDD_7") (pintype "input"))
      (node (ref "U9") (pin "8") (pinfunction "VDD/AVDD/VDDIO_8") (pintype "input"))
    )
    (net (code "40") (name "unconnected-(TP21-Pad1)") (class "Default")
      (node (ref "TP21") (pin "1") (pinfunction "1_1") (pintype "input+no_connect"))
    )
    (net (code "41") (name "unconnected-(U2-P43-Pad12)") (class "Default")
      (node (ref "U2") (pin "12") (pinfunction "P43_12") (pintype "input+no_connect"))
    )
    (net (code "42") (name "unconnected-(U9-DAC1O-Pad1)") (class "Default")
      (node (ref "U9") (pin "1") (pinfunction "DAC1O_1") (pintype "input+no_connect"))
    )
    (net (code "43") (name "unconnected-(U9-DAC3O-Pad4)") (class "Default")
      (node (ref "U9") (pin "4") (pinfunction "DAC3O_4") (pintype "input+no_connect"))
    )
    (net (code "44") (name "unconnected-(U9-OP2N-Pad22)") (class "Default")
      (node (ref "U9") (pin "22") (pinfunction "OP2N_22") (pintype "input+no_connect"))
    )
    (net (code "45") (name "unconnected-(U9-OP2O-Pad20)") (class "Default")
      (node (ref "U9") (pin "20") (pinfunction "OP2O_20") (pintype "input+no_connect"))
    )
    (net (code "46") (name "unconnected-(U9-PA1{slash}AIN1-Pad15)") (class "Default")
      (node (ref "U9") (pin "15") (pinfunction "PA1/AIN1_15") (pintype "input+no_connect"))
    )
    (net (code "47") (name "unconnected-(U9-PA3{slash}AIN0-Pad14)") (class "Default")
      (node (ref "U9") (pin "14") (pinfunction "PA3/AIN0_14") (pintype "input+no_connect"))
    )
    (net (code "48") (name "unconnected-(U11-NC-Pad2)") (class "Default")
      (node (ref "U11") (pin "2") (pinfunction "NC_2") (pintype "input+no_connect"))
    )
  )
)
